# s-radio_SCHEM.net
KiCad netlist of a schematic drawn in Altium Designer
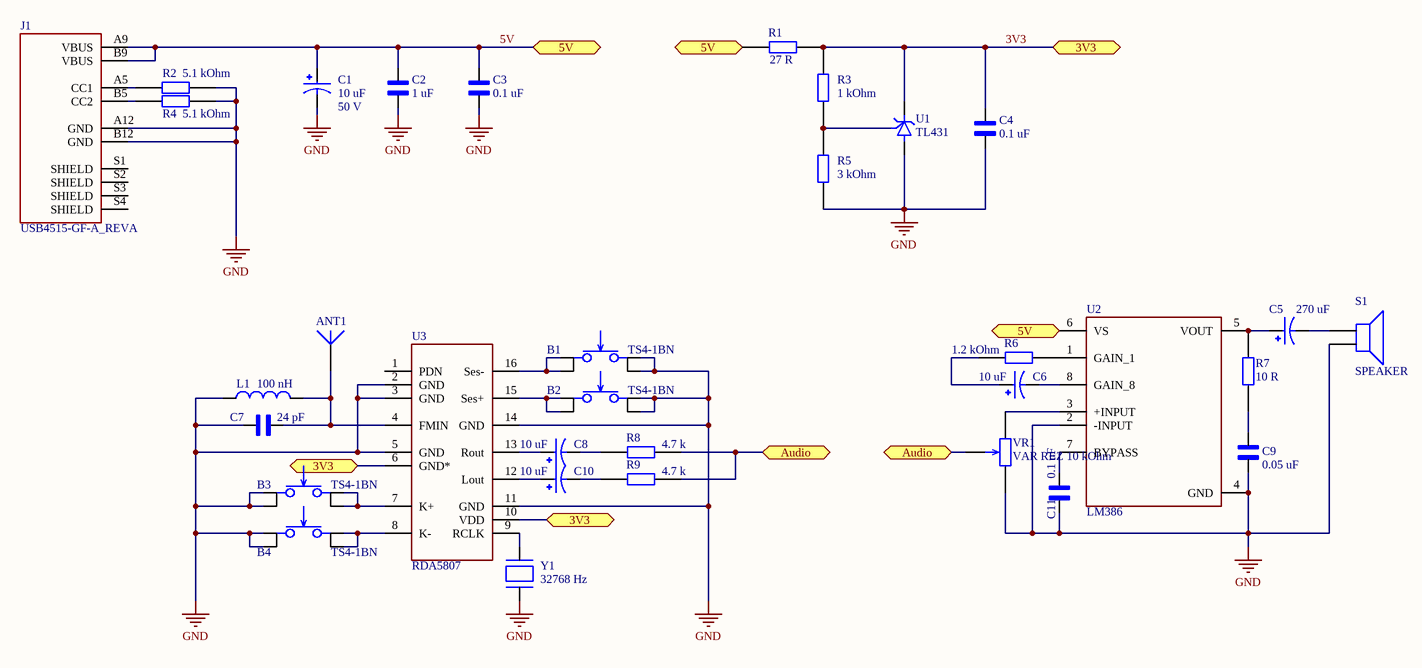
[diagram p0: s-radio_SCHEM.SchDoc]

(export (version "E")
  (design (tool "Eeschema 10.0.6"))
  (components
    (comp (ref "ANT1") (value "Antenna") (footprint "Antenna") (libsource (lib "sRadioLib") (part "Antenna")))
    (comp (ref "B1") (value "TS4-1BN") (footprint "TS4-1BN") (libsource (lib "sRadioLib") (part "TS4-1BN")))
    (comp (ref "B2") (value "TS4-1BN") (footprint "TS4-1BN") (libsource (lib "sRadioLib") (part "TS4-1BN")))
    (comp (ref "B3") (value "TS4-1BN") (footprint "TS4-1BN") (libsource (lib "sRadioLib") (part "TS4-1BN")))
    (comp (ref "B4") (value "TS4-1BN") (footprint "TS4-1BN") (libsource (lib "sRadioLib") (part "TS4-1BN")))
    (comp (ref "C1")
      (value "10 uF")
      (footprint "К50-35 5x7")
      (description "10 uF 50V Aluminum Electrolytic Capacitors Radial")
      (fields (field (name "MP") "К50-35") (field (name "VOLTAGE") "50 V"))
      (libsource (lib "") (part "К50-35_1"))
    )
    (comp (ref "C2")
      (value "1 uF")
      (footprint "CAP_0603")
      (fields (field (name "Comment") "CAP 0603 1 uF"))
      (libsource (lib "sRadioLib") (part "CAP 0603 1 uF"))
    )
    (comp (ref "C3")
      (value "0.1 uF")
      (footprint "CAP_0603")
      (fields (field (name "Comment") "CAP 0603 0.1 uF"))
      (libsource (lib "") (part "CAP 0603 0.1 uF_1"))
    )
    (comp (ref "C4")
      (value "0.1 uF")
      (footprint "CAP_0603")
      (fields (field (name "Comment") "CAP 0603 0.1 uF"))
      (libsource (lib "") (part "CAP 0603 0.1 uF_1"))
    )
    (comp (ref "C5")
      (value "270 uF")
      (footprint "CAPPRD350W60D800H1500")
      (description "270ÂµF 35V Aluminum Electrolytic Capacitors Radial, Can 8000 Hrs @ 105Â°C")
      (fields (field (name "MP") "EEUFR1V271L") (field (name "MF") "Panasonic"))
      (libsource (lib "sRadioLib") (part "CAP 270 uF"))
    )
    (comp (ref "C6")
      (value "10 uF")
      (footprint "К50-35 5x7")
      (description "10 uF 50V Aluminum Electrolytic Capacitors Radial")
      (fields (field (name "MP") "К50-35") (field (name "VOLTAGE") "50 V"))
      (libsource (lib "sRadioLib") (part "К50-35"))
    )
    (comp (ref "C7")
      (value "24 pF")
      (footprint "CAP_0805")
      (fields (field (name "MP") "GRM2165C1H240J") (field (name "Comment") "CAP 0805 24 pF"))
      (libsource (lib "sRadioLib") (part "CAP 0805 24 pF"))
    )
    (comp (ref "C8")
      (value "10 uF")
      (footprint "К50-35 5x7")
      (description "10 uF 50V Aluminum Electrolytic Capacitors Radial")
      (fields (field (name "MP") "К50-35") (field (name "VOLTAGE") "50 V"))
      (libsource (lib "sRadioLib") (part "К50-35"))
    )
    (comp (ref "C9")
      (value "0.05 uF")
      (footprint "CAP_1206")
      (description "Ceramic Capacitor 0.05uf, 50v, X7r, 5%, 1206, Full Reel")
      (fields
        (field (name "MP") "12065C503JAT2A")
        (field (name "DIGI-KEY_PART_NUMBER") "478-12065C503JAT2ACT-ND")
      )
      (libsource (lib "sRadioLib") (part "CAP 0.05uF 1206"))
    )
    (comp (ref "C10")
      (value "10 uF")
      (footprint "К50-35 5x7")
      (description "10 uF 50V Aluminum Electrolytic Capacitors Radial")
      (fields (field (name "MP") "К50-35") (field (name "VOLTAGE") "50 V"))
      (libsource (lib "sRadioLib") (part "К50-35"))
    )
    (comp (ref "C11")
      (value "0.1 uF")
      (footprint "CAP_0603")
      (fields (field (name "Comment") "CAP 0603 0.1 uF"))
      (libsource (lib "sRadioLib") (part "CAP 0603 0.1 uF"))
    )
    (comp (ref "J1")
      (value "USB4515-GF-A_REVA")
      (footprint "GCT_USB4515-GF-A_REVA")
      (description "Type C USB Charging Connector")
      (fields
        (field (name "MF") "Global Connector Technology")
        (field (name "DIGI-KEY_PART_NUMBER") "2073-USB4515-GF-ATR-ND")
      )
      (libsource (lib "sRadioLib") (part "USB4515-GF-A_REVA"))
    )
    (comp (ref "L1")
      (value "100 nH")
      (footprint "L_0805")
      (description "Ind RF Chip Wirewound 100nH 5% 150MHz 65Q-Factor 400mA 0805 Embossed T/R")
      (fields (field (name "MP") "LQW2BASR10J00L"))
      (libsource (lib "sRadioLib") (part "LQW2BASR10J00L"))
    )
    (comp (ref "R1")
      (value "27 R")
      (footprint "RES_2512")
      (description "27 Ohm")
      (fields (field (name "MF") "{'manufacturer': u'Yageo'}") (field (name "MP") "0.125Вт 0805 4.7 кОм"))
      (libsource (lib "sRadioLib") (part "RES 27 Ohm"))
    )
    (comp (ref "R2")
      (value "5.1 kOhm")
      (footprint "RES_0603")
      (fields
        (field (name "MF") "{'manufacturer': u'Yageo'}")
        (field (name "MP") "0.1Вт 0603 5.1 кОм")
        (field (name "TOLERANCE") "5%")
      )
      (libsource (lib "sRadioLib") (part "RES 5.1 kOhm"))
    )
    (comp (ref "R3")
      (value "1 kOhm")
      (footprint "RES_0603")
      (fields
        (field (name "MF") "{'manufacturer': u'Yageo'}")
        (field (name "MP") "0.1Вт 0603 1 кОм")
        (field (name "TOLERANCE") "5%")
      )
      (libsource (lib "sRadioLib") (part "RES 1 kOhm"))
    )
    (comp (ref "R4")
      (value "5.1 kOhm")
      (footprint "RES_0603")
      (fields
        (field (name "MF") "{'manufacturer': u'Yageo'}")
        (field (name "MP") "0.1Вт 0603 5.1 кОм")
        (field (name "TOLERANCE") "5%")
      )
      (libsource (lib "sRadioLib") (part "RES 5.1 kOhm"))
    )
    (comp (ref "R5")
      (value "3 kOhm")
      (footprint "RES_0603")
      (fields
        (field (name "MF") "{'manufacturer': u'Yageo'}")
        (field (name "MP") "0.1Вт 0603 3 кОм")
        (field (name "TOLERANCE") "1%")
      )
      (libsource (lib "sRadioLib") (part "RES 3 kOhm"))
    )
    (comp (ref "R6")
      (value "1.2 kOhm")
      (footprint "RES_0603")
      (fields
        (field (name "MF") "{'manufacturer': u'Yageo'}")
        (field (name "MP") "0.1Вт 0603 1.2 кОм")
        (field (name "TOLERANCE") "5%")
      )
      (libsource (lib "sRadioLib") (part "RES 1.2 kOhm"))
    )
    (comp (ref "R7")
      (value "10 R")
      (footprint "RES_0603")
      (description "10 Ohm")
      (fields (field (name "MF") "{'manufacturer': u'Yageo'}") (field (name "MP") "0.1Вт 0603 10 Ом"))
      (libsource (lib "sRadioLib") (part "RES 10 R"))
    )
    (comp (ref "R8")
      (value "4.7 k")
      (footprint "RES_0805")
      (description "4.7 kOhm")
      (fields (field (name "MF") "{'manufacturer': u'Yageo'}") (field (name "MP") "0.125Вт 0805 4.7 кОм"))
      (libsource (lib "sRadioLib") (part "RES 4.7 kOhm"))
    )
    (comp (ref "R9")
      (value "4.7 k")
      (footprint "RES_0805")
      (description "4.7 kOhm")
      (fields (field (name "MF") "{'manufacturer': u'Yageo'}") (field (name "MP") "0.125Вт 0805 4.7 кОм"))
      (libsource (lib "sRadioLib") (part "RES 4.7 kOhm"))
    )
    (comp (ref "S1") (value "SPEAKER") (footprint "SPEAKER") (libsource (lib "sRadioLib") (part "SPEAKER")))
    (comp (ref "U1")
      (value "TL431")
      (footprint "SOT95P237X112-3N")
      (description "Ic, Tl431ilp, Tl431, Tl431a, Tl4 31b, Tl432, Tl432a, Tl432b<Nv")
      (libsource (lib "sRadioLib") (part "TL431"))
    )
    (comp (ref "U2")
      (value "LM386")
      (footprint "dip-8")
      (fields (field (name "MP") "LM386N-3/NOPB"))
      (libsource (lib "sRadioLib") (part "LM386"))
    )
    (comp (ref "U3") (value "RDA5807") (footprint "SOP-16") (libsource (lib "sRadioLib") (part "RDA5807")))
    (comp (ref "VR1")
      (value "VAR REZ 10 kOhm")
      (footprint "P160")
      (fields (field (name "MF") "{'manufacturer': u'Yageo'}"))
      (libsource (lib "sRadioLib") (part "VAR REZ 10 kOhm"))
    )
    (comp (ref "Y1")
      (value "32768 Hz")
      (footprint "XTAL_NX3215SA-32.768K-STD-MUA-8")
      (description "32.768 kHz Â±20ppm Crystal 12.5pF 70 kOhms 2-SMD, No Lead")
      (fields (field (name "MF") "NDK America,") (field (name "MP") "NX3215SA-32.768K-STD-MUA-8"))
      (libsource (lib "sRadioLib") (part "NX3215SA-32.768K-STD-MUA-8"))
    )
  )
  (nets
    (net (code "1") (name "/3V3") (class "Default")
      (node (ref "C4") (pin "2") (pinfunction "2_2") (pintype "passive"))
      (node (ref "R1") (pin "2") (pinfunction "2_2") (pintype "passive"))
      (node (ref "R3") (pin "2") (pinfunction "2_2") (pintype "passive"))
      (node (ref "U1") (pin "3") (pinfunction "C_3") (pintype "passive"))
      (node (ref "U3") (pin "10") (pinfunction "VDD_10") (pintype "passive"))
      (node (ref "U3") (pin "6") (pinfunction "GND*_6") (pintype "passive"))
    )
    (net (code "2") (name "/5V") (class "Default")
      (node (ref "C1") (pin "P") (pinfunction "P_P") (pintype "passive"))
      (node (ref "C2") (pin "2") (pinfunction "2_2") (pintype "passive"))
      (node (ref "C3") (pin "2") (pinfunction "2_2") (pintype "passive"))
      (node (ref "J1") (pin "A9") (pinfunction "VBUS_A9") (pintype "passive"))
      (node (ref "J1") (pin "B9") (pinfunction "VBUS_B9") (pintype "passive"))
      (node (ref "R1") (pin "1") (pinfunction "1_1") (pintype "passive"))
      (node (ref "U2") (pin "6") (pinfunction "VS_6") (pintype "passive"))
    )
    (net (code "3") (name "/Audio") (class "Default")
      (node (ref "R8") (pin "2") (pinfunction "2_2") (pintype "passive"))
      (node (ref "R9") (pin "2") (pinfunction "2_2") (pintype "passive"))
      (node (ref "VR1") (pin "2") (pinfunction "2_2") (pintype "passive"))
    )
    (net (code "4") (name "GND") (class "Default")
      (node (ref "B1") (pin "3") (pinfunction "3_3") (pintype "passive"))
      (node (ref "B1") (pin "4") (pinfunction "4_4") (pintype "passive"))
      (node (ref "B2") (pin "3") (pinfunction "3_3") (pintype "passive"))
      (node (ref "B2") (pin "4") (pinfunction "4_4") (pintype "passive"))
      (node (ref "B3") (pin "1") (pinfunction "1_1") (pintype "passive"))
      (node (ref "B3") (pin "2") (pinfunction "2_2") (pintype "passive"))
      (node (ref "B4") (pin "1") (pinfunction "1_1") (pintype "passive"))
      (node (ref "B4") (pin "2") (pinfunction "2_2") (pintype "passive"))
      (node (ref "C1") (pin "N") (pinfunction "N_N") (pintype "passive"))
      (node (ref "C11") (pin "2") (pinfunction "2_2") (pintype "passive"))
      (node (ref "C2") (pin "1") (pinfunction "1_1") (pintype "passive"))
      (node (ref "C3") (pin "1") (pinfunction "1_1") (pintype "passive"))
      (node (ref "C4") (pin "1") (pinfunction "1_1") (pintype "passive"))
      (node (ref "C7") (pin "1") (pinfunction "1_1") (pintype "passive"))
      (node (ref "C9") (pin "1") (pinfunction "1_1") (pintype "passive"))
      (node (ref "J1") (pin "A12") (pinfunction "GND_A12") (pintype "power_in"))
      (node (ref "J1") (pin "B12") (pinfunction "GND_B12") (pintype "power_in"))
      (node (ref "L1") (pin "1") (pinfunction "1_1") (pintype "passive"))
      (node (ref "R2") (pin "2") (pinfunction "2_2") (pintype "passive"))
      (node (ref "R4") (pin "2") (pinfunction "2_2") (pintype "passive"))
      (node (ref "R5") (pin "1") (pinfunction "1_1") (pintype "passive"))
      (node (ref "S1") (pin "2") (pinfunction "2_2") (pintype "passive"))
      (node (ref "U1") (pin "2") (pinfunction "A_2") (pintype "passive"))
      (node (ref "U2") (pin "2") (pinfunction "-INPUT_2") (pintype "passive"))
      (node (ref "U2") (pin "4") (pinfunction "GND_4") (pintype "passive"))
      (node (ref "U3") (pin "11") (pinfunction "GND_11") (pintype "passive"))
      (node (ref "U3") (pin "14") (pinfunction "GND_14") (pintype "passive"))
      (node (ref "U3") (pin "2") (pinfunction "GND_2") (pintype "passive"))
      (node (ref "U3") (pin "3") (pinfunction "GND_3") (pintype "passive"))
      (node (ref "U3") (pin "5") (pinfunction "GND_5") (pintype "passive"))
      (node (ref "VR1") (pin "1") (pinfunction "1_1") (pintype "passive"))
      (node (ref "Y1") (pin "1") (pinfunction "1_1") (pintype "passive"))
    )
    (net (code "5") (name "Net-(C5-PadN)") (class "Default")
      (node (ref "C5") (pin "N") (pinfunction "N_N") (pintype "passive"))
      (node (ref "S1") (pin "1") (pinfunction "1_1") (pintype "passive"))
    )
    (net (code "6") (name "Net-(C6-PadP)") (class "Default")
      (node (ref "C6") (pin "P") (pinfunction "P_P") (pintype "passive"))
      (node (ref "R6") (pin "1") (pinfunction "1_1") (pintype "passive"))
    )
    (net (code "7") (name "Net-(C8-PadN)") (class "Default")
      (node (ref "C8") (pin "N") (pinfunction "N_N") (pintype "passive"))
      (node (ref "R8") (pin "1") (pinfunction "1_1") (pintype "passive"))
    )
    (net (code "8") (name "Net-(C9-Pad2)") (class "Default")
      (node (ref "C9") (pin "2") (pinfunction "2_2") (pintype "passive"))
      (node (ref "R7") (pin "1") (pinfunction "1_1") (pintype "passive"))
    )
    (net (code "9") (name "Net-(C10-PadN)") (class "Default")
      (node (ref "C10") (pin "N") (pinfunction "N_N") (pintype "passive"))
      (node (ref "R9") (pin "1") (pinfunction "1_1") (pintype "passive"))
    )
    (net (code "10") (name "Net-(J1-CC1)") (class "Default")
      (node (ref "J1") (pin "A5") (pinfunction "CC1_A5") (pintype "passive"))
      (node (ref "R2") (pin "1") (pinfunction "1_1") (pintype "passive"))
    )
    (net (code "11") (name "Net-(J1-CC2)") (class "Default")
      (node (ref "J1") (pin "B5") (pinfunction "CC2_B5") (pintype "passive"))
      (node (ref "R4") (pin "1") (pinfunction "1_1") (pintype "passive"))
    )
    (net (code "12") (name "Net-(U1-REF)") (class "Default")
      (node (ref "R3") (pin "1") (pinfunction "1_1") (pintype "passive"))
      (node (ref "R5") (pin "2") (pinfunction "2_2") (pintype "passive"))
      (node (ref "U1") (pin "1") (pinfunction "REF_1") (pintype "passive"))
    )
    (net (code "13") (name "Net-(U2-+INPUT)") (class "Default")
      (node (ref "U2") (pin "3") (pinfunction "+INPUT_3") (pintype "passive"))
      (node (ref "VR1") (pin "3") (pinfunction "3_3") (pintype "passive"))
    )
    (net (code "14") (name "Net-(U2-BYPASS)") (class "Default")
      (node (ref "C11") (pin "1") (pinfunction "1_1") (pintype "passive"))
      (node (ref "U2") (pin "7") (pinfunction "BYPASS_7") (pintype "passive"))
    )
    (net (code "15") (name "Net-(U2-GAIN_1)") (class "Default")
      (node (ref "R6") (pin "2") (pinfunction "2_2") (pintype "passive"))
      (node (ref "U2") (pin "1") (pinfunction "GAIN_1_1") (pintype "passive"))
    )
    (net (code "16") (name "Net-(U2-GAIN_8)") (class "Default")
      (node (ref "C6") (pin "N") (pinfunction "N_N") (pintype "passive"))
      (node (ref "U2") (pin "8") (pinfunction "GAIN_8_8") (pintype "passive"))
    )
    (net (code "17") (name "Net-(U2-VOUT)") (class "Default")
      (node (ref "C5") (pin "P") (pinfunction "P_P") (pintype "passive"))
      (node (ref "R7") (pin "2") (pinfunction "2_2") (pintype "passive"))
      (node (ref "U2") (pin "5") (pinfunction "VOUT_5") (pintype "passive"))
    )
    (net (code "18") (name "Net-(U3-FMIN)") (class "Default")
      (node (ref "ANT1") (pin "1") (pinfunction "1_1") (pintype "passive"))
      (node (ref "C7") (pin "2") (pinfunction "2_2") (pintype "passive"))
      (node (ref "L1") (pin "2") (pinfunction "2_2") (pintype "passive"))
      (node (ref "U3") (pin "4") (pinfunction "FMIN_4") (pintype "passive"))
    )
    (net (code "19") (name "Net-(U3-K+)") (class "Default")
      (node (ref "B3") (pin "3") (pinfunction "3_3") (pintype "passive"))
      (node (ref "B3") (pin "4") (pinfunction "4_4") (pintype "passive"))
      (node (ref "U3") (pin "7") (pinfunction "K+_7") (pintype "passive"))
    )
    (net (code "20") (name "Net-(U3-K-)") (class "Default")
      (node (ref "B4") (pin "3") (pinfunction "3_3") (pintype "passive"))
      (node (ref "B4") (pin "4") (pinfunction "4_4") (pintype "passive"))
      (node (ref "U3") (pin "8") (pinfunction "K-_8") (pintype "passive"))
    )
    (net (code "21") (name "Net-(U3-Lout)") (class "Default")
      (node (ref "C10") (pin "P") (pinfunction "P_P") (pintype "passive"))
      (node (ref "U3") (pin "12") (pinfunction "Lout_12") (pintype "passive"))
    )
    (net (code "22") (name "Net-(U3-RCLK)") (class "Default")
      (node (ref "U3") (pin "9") (pinfunction "RCLK_9") (pintype "passive"))
      (node (ref "Y1") (pin "2") (pinfunction "2_2") (pintype "passive"))
    )
    (net (code "23") (name "Net-(U3-Rout)") (class "Default")
      (node (ref "C8") (pin "P") (pinfunction "P_P") (pintype "passive"))
      (node (ref "U3") (pin "13") (pinfunction "Rout_13") (pintype "passive"))
    )
    (net (code "24") (name "Net-(U3-Ses+)") (class "Default")
      (node (ref "B2") (pin "1") (pinfunction "1_1") (pintype "passive"))
      (node (ref "B2") (pin "2") (pinfunction "2_2") (pintype "passive"))
      (node (ref "U3") (pin "15") (pinfunction "Ses+_15") (pintype "passive"))
    )
    (net (code "25") (name "Net-(U3-Ses-)") (class "Default")
      (node (ref "B1") (pin "1") (pinfunction "1_1") (pintype "passive"))
      (node (ref "B1") (pin "2") (pinfunction "2_2") (pintype "passive"))
      (node (ref "U3") (pin "16") (pinfunction "Ses-_16") (pintype "passive"))
    )
    (net (code "26") (name "unconnected-(J1-SHIELD-PadS1)") (class "Default")
      (node (ref "J1") (pin "S1") (pinfunction "SHIELD_S1") (pintype "power_in"))
    )
    (net (code "27") (name "unconnected-(J1-SHIELD-PadS2)") (class "Default")
      (node (ref "J1") (pin "S2") (pinfunction "SHIELD_S2") (pintype "power_in"))
    )
    (net (code "28") (name "unconnected-(J1-SHIELD-PadS3)") (class "Default")
      (node (ref "J1") (pin "S3") (pinfunction "SHIELD_S3") (pintype "power_in"))
    )
    (net (code "29") (name "unconnected-(J1-SHIELD-PadS4)") (class "Default")
      (node (ref "J1") (pin "S4") (pinfunction "SHIELD_S4") (pintype "power_in"))
    )
    (net (code "30") (name "unconnected-(U3-PDN-Pad1)") (class "Default")
      (node (ref "U3") (pin "1") (pinfunction "PDN_1") (pintype "passive"))
    )
  )
)
